# Protolink_Agro_LoRa_Schematic.net
KiCad netlist of a schematic drawn in Altium Designer
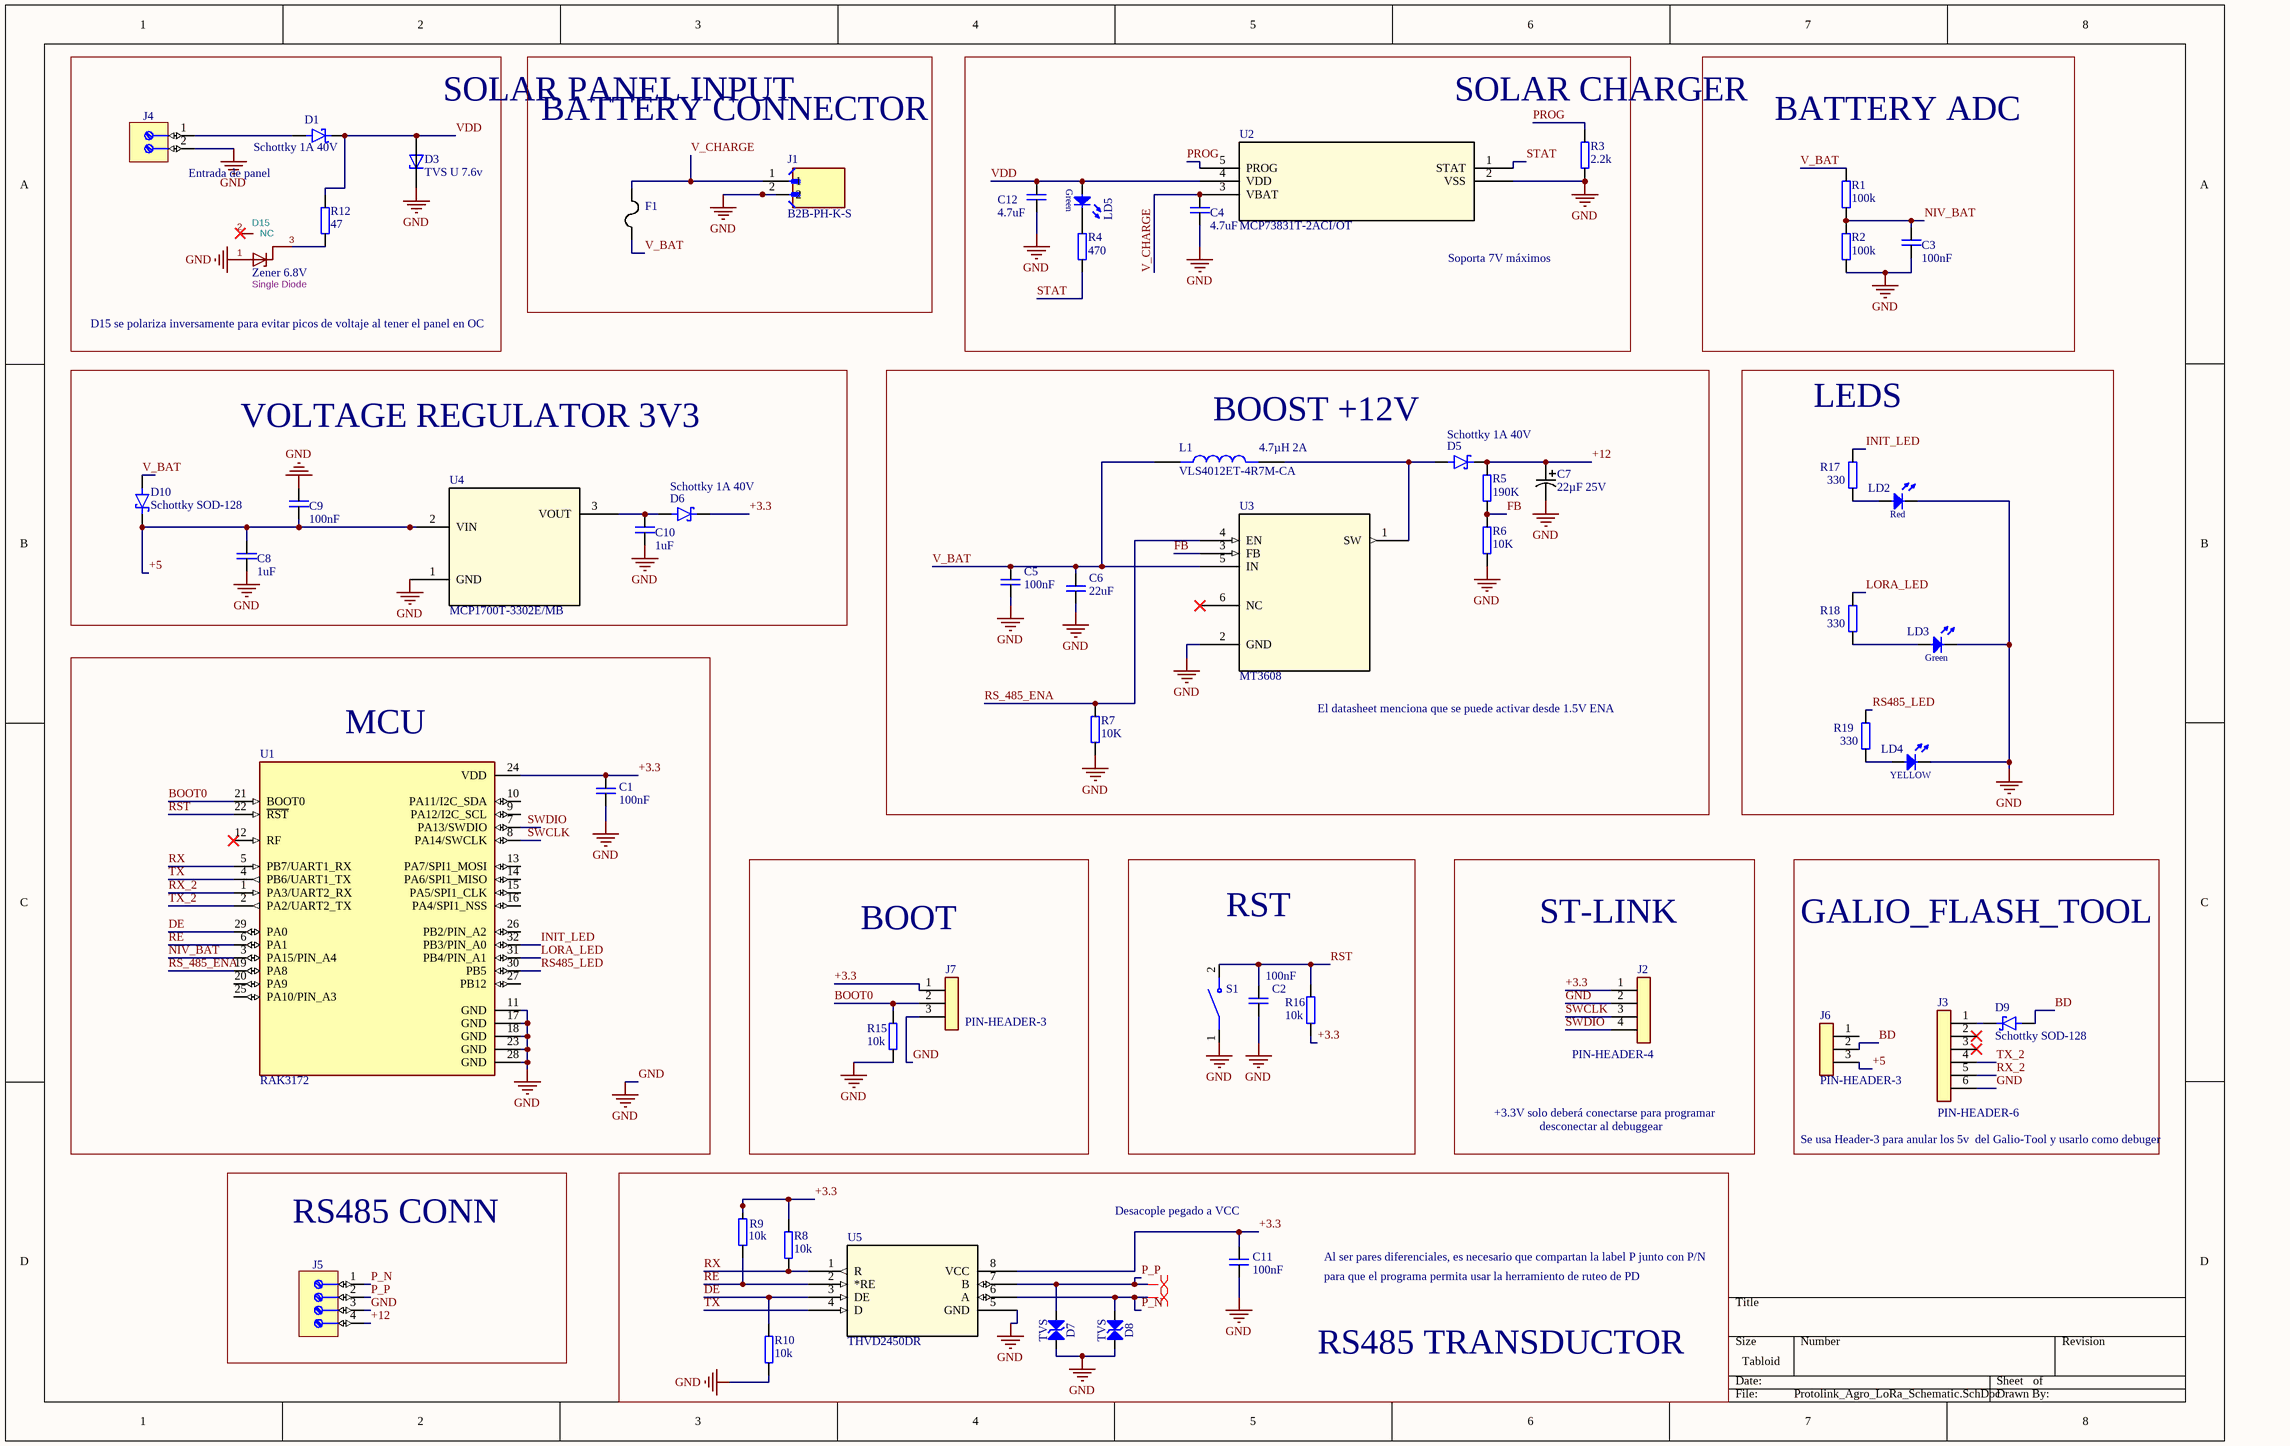
[diagram p0: Protolink_Agro_LoRa_Schematic.SchDoc]

(export (version "E")
  (design (tool "Eeschema 10.0.6"))
  (components
    (comp (ref "C1")
      (value "100nF")
      (footprint "CAPC2012X110N")
      (description "CAPACITOR, 0805")
      (fields (field (name "MF") "KEMET") (field (name "MP") "C0805C125K4RACTU"))
      (libsource (lib "") (part "C0805C125K4RACTU_1"))
    )
    (comp (ref "C2")
      (value "100nF")
      (footprint "CAPC2012X110N")
      (description "CAPACITOR, 0805")
      (fields (field (name "MF") "KEMET") (field (name "MP") "C0805C125K4RACTU"))
      (libsource (lib "") (part "C0805C125K4RACTU_1"))
    )
    (comp (ref "C3")
      (value "100nF")
      (footprint "CAPC2012X110N")
      (description "CAPACITOR, 0805")
      (fields (field (name "MF") "KEMET") (field (name "MP") "C0805C125K4RACTU"))
      (libsource (lib "") (part "C0805C125K4RACTU_1"))
    )
    (comp (ref "C4")
      (value "4.7uF")
      (footprint "CAPC2012X110N")
      (description "CAPACITOR, 0805")
      (fields (field (name "MF") "KEMET") (field (name "MP") "C0805C125K4RACTU"))
      (libsource (lib "Galio-complete") (part "C0805C125K4RACTU"))
    )
    (comp (ref "C5")
      (value "100nF")
      (footprint "CAPC2012X110N")
      (description "CAPACITOR, 0805")
      (fields (field (name "MF") "KEMET") (field (name "MP") "C0805C125K4RACTU"))
      (libsource (lib "") (part "C0805C125K4RACTU_1"))
    )
    (comp (ref "C6")
      (value "22uF")
      (footprint "CAPC2012X110N")
      (description "CAPACITOR, 0805")
      (fields (field (name "MF") "KEMET") (field (name "MP") "C0805C125K4RACTU"))
      (libsource (lib "") (part "C0805C125K4RACTU_1"))
    )
    (comp (ref "C7")
      (value "22µF 25V")
      (footprint "CAP_EEFK_C_PAN")
      (description "Capacitor electrolítico aluminio SMD")
      (fields
        (field (name "MANUFACTURER_PART_NUMBER") "EEE-FK1E220AR")
        (field (name "COPYRIGHT") "Copyright (C) 2026 Ultra Librarian. All rights reserved.")
      )
      (libsource (lib "Galio-complete") (part "EEE-FK1E220AR"))
    )
    (comp (ref "C8")
      (value "1uF")
      (footprint "CAPC2012X110N")
      (description "CAPACITOR, 0805")
      (fields (field (name "MF") "KEMET") (field (name "MP") "C0805C125K4RACTU"))
      (libsource (lib "") (part "C0805C125K4RACTU_1"))
    )
    (comp (ref "C9")
      (value "100nF")
      (footprint "CAPC2012X110N")
      (description "CAPACITOR, 0805")
      (fields (field (name "MF") "KEMET") (field (name "MP") "C0805C125K4RACTU"))
      (libsource (lib "") (part "C0805C125K4RACTU_1"))
    )
    (comp (ref "C10")
      (value "1uF")
      (footprint "CAPC2012X110N")
      (description "CAPACITOR, 0805")
      (fields (field (name "MF") "KEMET") (field (name "MP") "C0805C125K4RACTU"))
      (libsource (lib "") (part "C0805C125K4RACTU_1"))
    )
    (comp (ref "C11")
      (value "100nF")
      (footprint "CAPC2012X110N")
      (description "CAPACITOR, 0805")
      (fields (field (name "MF") "KEMET") (field (name "MP") "C0805C125K4RACTU"))
      (libsource (lib "") (part "C0805C125K4RACTU_1"))
    )
    (comp (ref "C12")
      (value "4.7uF")
      (footprint "CAPC2012X110N")
      (description "CAPACITOR, 0805")
      (fields (field (name "MF") "KEMET") (field (name "MP") "C0805C125K4RACTU"))
      (libsource (lib "Galio-complete") (part "C0805C125K4RACTU"))
    )
    (comp (ref "D1")
      (value "Schottky 1A 40V")
      (footprint "SODFL4725X110N")
      (description "Diode Schottky 40V 2A Surface Mount SOD-128/CFP5")
      (fields (field (name "MF") "Nexperia USA") (field (name "MP") "PMEG4020ETP,115"))
      (libsource (lib "Galio-complete") (part "PMEG4020ETP,115"))
    )
    (comp (ref "D3")
      (value "TVS U 7.6v")
      (footprint "DIOM4325X250N")
      (description "11 TVS Diode Surface Mount DO-214AC (SMA)")
      (fields (field (name "MF") "Bourns") (field (name "MP") "SMAJ11A"))
      (libsource (lib "Galio-complete") (part "SMAJ11A"))
    )
    (comp (ref "D5")
      (value "Schottky 1A 40V")
      (footprint "SODFL4725X110N")
      (description "Diode Schottky 40V 2A Surface Mount SOD-128/CFP5")
      (fields (field (name "MF") "Nexperia USA") (field (name "MP") "PMEG4020ETP,115"))
      (libsource (lib "Galio-complete") (part "PMEG4020ETP,115"))
    )
    (comp (ref "D6")
      (value "Schottky 1A 40V")
      (footprint "SODFL4725X110N")
      (description "Diode Schottky 40V 2A Surface Mount SOD-128/CFP5")
      (fields (field (name "MF") "Nexperia USA") (field (name "MP") "PMEG4020ETP,115"))
      (libsource (lib "Galio-complete") (part "PMEG4020ETP,115"))
    )
    (comp (ref "D7")
      (value "TVS")
      (footprint "DIOM5126X229N")
      (description "Transient Voltage Suppressor Diode (Bi-Directional)")
      (libsource (lib "Galio-complete") (part "Diode TVS Bi-Directional"))
    )
    (comp (ref "D8")
      (value "TVS")
      (footprint "DIOM5126X229N")
      (description "Transient Voltage Suppressor Diode (Bi-Directional)")
      (libsource (lib "Galio-complete") (part "Diode TVS Bi-Directional"))
    )
    (comp (ref "D9")
      (value "Schottky SOD-128")
      (footprint "SODFL4725X110N")
      (description "Diode Schottky 40V 2A Surface Mount SOD-128/CFP5")
      (fields (field (name "MF") "Nexperia USA") (field (name "MP") "PMEG4020ETP,115"))
      (libsource (lib "Galio-complete") (part "PMEG4020ETP,115"))
    )
    (comp (ref "D10")
      (value "Schottky SOD-128")
      (footprint "SODFL4725X110N")
      (description "Diode Schottky 40V 2A Surface Mount SOD-128/CFP5")
      (fields (field (name "MF") "Nexperia USA") (field (name "MP") "PMEG4020ETP,115"))
      (libsource (lib "Galio-complete") (part "PMEG4020ETP,115"))
    )
    (comp (ref "D15")
      (value "Zener 6.8V")
      (footprint "SOT-23")
      (fields (field (name "ALTIUM_VALUE") "Single Diode"))
      (libsource (lib "Galio-complete") (part "Zener-Diode_NC"))
    )
    (comp (ref "F1")
      (value "~")
      (footprint "FUSE_MF-MSMF07524-2_BRN")
      (description "Fuse")
      (fields
        (field (name "MANUFACTURER_PART_NUMBER") "MF-MSMF075/24-2")
        (field (name "COPYRIGHT") "Copyright (C) 2026 Ultra Librarian. All rights reserved.")
      )
      (libsource (lib "Galio-complete") (part "MF-MSMF07524-2"))
    )
    (comp (ref "J1")
      (value "B2B-PH-K-S")
      (footprint "JST_B2B-PH-K-S")
      (description "Connector Header Through Hole 2 position 0.079 (2.00mm)")
      (fields (field (name "MF") "JST Sales America Inc."))
      (libsource (lib "Galio-connectors") (part "B2B-PH-K-S"))
    )
    (comp (ref "J2")
      (value "PIN-HEADER-4")
      (footprint "PIN-HEADER-4-MALE")
      (fields (field (name "MP") "MTSW-104-06-T-S-100"))
      (libsource (lib "Galio-connectors") (part "PIN-HEADER-4"))
    )
    (comp (ref "J3")
      (value "PIN-HEADER-6")
      (footprint "PIN-HEADER-6-FEMALE")
      (fields (field (name "MP") "MTSW-106-06-T-S-100"))
      (libsource (lib "Galio-connectors") (part "PIN-HEADER-6"))
    )
    (comp (ref "J4")
      (value "TRT2")
      (footprint "TRT_2_KF301")
      (description "Terminal Block, 2 Positions, Screw Connection")
      (libsource (lib "Galio-connectors") (part "TRT_2"))
    )
    (comp (ref "J5")
      (value "TRT4")
      (footprint "TRT_4_ KF301")
      (description "TRT_4")
      (libsource (lib "Galio-connectors") (part "TRT_4"))
    )
    (comp (ref "J6")
      (value "PIN-HEADER-3")
      (footprint "PIN-HEADER-3-MALE")
      (fields (field (name "MP") "MTSW-103-06-T-S-190"))
      (libsource (lib "Galio-connectors") (part "PIN-HEADER-3"))
    )
    (comp (ref "J7")
      (value "PIN-HEADER-3")
      (footprint "PIN-HEADER-3-MALE")
      (fields (field (name "MP") "MTSW-103-06-T-S-190"))
      (libsource (lib "") (part "PIN-HEADER-3_1"))
    )
    (comp (ref "L1")
      (value "VLS4012ET-4R7M-CA")
      (footprint "IND_VLS4012ET-4R7M-CA")
      (description "4.7 µH Shielded Drum Core, Wirewound Inductor 1.9 A 118mOhm Max Nonstandard")
      (fields (field (name "MF") "TDK"))
      (libsource (lib "Galio-complete") (part "VLS4012ET-4R7M-CA"))
    )
    (comp (ref "LD2")
      (value "~")
      (footprint "LEDC2012X70N")
      (description "LED Red 0805")
      (libsource (lib "Galio-complete") (part "LED Red 0805"))
    )
    (comp (ref "LD3")
      (value "~")
      (footprint "LEDC2012X70N")
      (description "LED Green 0805")
      (libsource (lib "Galio-complete") (part "LED Green 0805"))
    )
    (comp (ref "LD4")
      (value "~")
      (footprint "LEDC2012X70N")
      (description "LED Yellow 0805")
      (libsource (lib "Galio-complete") (part "LED Yellow 0805"))
    )
    (comp (ref "LD5")
      (value "~")
      (footprint "LEDC2012X70N")
      (description "LED Green 0805")
      (libsource (lib "Galio-complete") (part "LED Green 0805"))
    )
    (comp (ref "R1")
      (value "100k")
      (footprint "RESC2013X84N")
      (libsource (lib "Galio-complete") (part "RES"))
    )
    (comp (ref "R2")
      (value "100k")
      (footprint "RESC2013X84N")
      (libsource (lib "Galio-complete") (part "RES"))
    )
    (comp (ref "R3")
      (value "2.2k")
      (footprint "RESC2013X84N")
      (libsource (lib "Galio-complete") (part "RES"))
    )
    (comp (ref "R4") (value "470") (footprint "RESC2013X84N") (libsource (lib "Galio-complete") (part "RES")))
    (comp (ref "R5")
      (value "190K")
      (footprint "RESC2013X84N")
      (libsource (lib "Galio-complete") (part "RES"))
    )
    (comp (ref "R6") (value "10K") (footprint "RESC2013X84N") (libsource (lib "Galio-complete") (part "RES")))
    (comp (ref "R7") (value "10K") (footprint "RESC2013X84N") (libsource (lib "Galio-complete") (part "RES")))
    (comp (ref "R8") (value "10k") (footprint "RESC2013X84N") (libsource (lib "Galio-complete") (part "RES")))
    (comp (ref "R9") (value "10k") (footprint "RESC2013X84N") (libsource (lib "Galio-complete") (part "RES")))
    (comp (ref "R10")
      (value "10k")
      (footprint "RESC2013X84N")
      (libsource (lib "Galio-complete") (part "RES"))
    )
    (comp (ref "R12") (value "47") (footprint "RESC2013X84N") (libsource (lib "Galio-complete") (part "RES")))
    (comp (ref "R15")
      (value "10k")
      (footprint "RESC2013X84N")
      (libsource (lib "Galio-complete") (part "RES"))
    )
    (comp (ref "R16")
      (value "10k")
      (footprint "RESC2013X84N")
      (libsource (lib "Galio-complete") (part "RES"))
    )
    (comp (ref "R17")
      (value "330")
      (footprint "RESC2013X84N")
      (libsource (lib "Galio-complete") (part "RES"))
    )
    (comp (ref "R18")
      (value "330")
      (footprint "RESC2013X84N")
      (libsource (lib "Galio-complete") (part "RES"))
    )
    (comp (ref "R19")
      (value "330")
      (footprint "RESC2013X84N")
      (libsource (lib "Galio-complete") (part "RES"))
    )
    (comp (ref "S1")
      (value "~")
      (footprint "SWITCH-SMD-4x3mm")
      (fields (field (name "MF") "Xunpu") (field (name "MP") "TS-1088-AR02016"))
      (libsource (lib "Galio-complete") (part "SWITCH-SMD-4x3mm"))
    )
    (comp (ref "U1")
      (value "RAK3172")
      (footprint "XCVR_RAK3172")
      (fields (field (name "MF") "Shenzhen RAKwireless Technology Co.,Ltd."))
      (libsource (lib "Galio-modules") (part "RAK3172"))
    )
    (comp (ref "U2")
      (value "MCP73831T-2ACI/OT")
      (footprint "SOT-23-5_MC_MCH-M")
      (description "Series Single-Cell Li-Ion/Li-Polymer Battery Charge Controller")
      (fields (field (name "COPYRIGHT") "Copyright (C) 2025 Ultra Librarian. All rights reserved."))
      (libsource (lib "Galio-complete") (part "MCP73831T-2ACIOT"))
    )
    (comp (ref "U3")
      (value "MT3608")
      (footprint "TSOT23-6SOT23-6_AER")
      (description "DC-DC step-up")
      (fields (field (name "COPYRIGHT") "Copyright (C) 2025 Ultra Librarian. All rights reserved."))
      (libsource (lib "Galio-complete") (part "MT3608"))
    )
    (comp (ref "U4")
      (value "MCP1700T-3302E/MB")
      (footprint "SOT-89_3MC_MCH")
      (description "Linear Voltage Regulators")
      (fields (field (name "COPYRIGHT") "Copyright (C) 2026 Ultra Librarian. All rights reserved."))
      (libsource (lib "Galio-complete") (part "MCP1700T-3302EMB"))
    )
    (comp (ref "U5")
      (value "THVD2450DR")
      (footprint "SOIC8-N_MC")
      (description "Transceiver Half RS422, RS485 SOIC-8")
      (fields (field (name "COPYRIGHT") "Copyright (C) 2025 Ultra Librarian. All rights reserved."))
      (libsource (lib "Galio-complete") (part "THVD2450DR"))
    )
  )
  (nets
    (net (code "1") (name "/+3.3") (class "Default")
      (node (ref "C1") (pin "2") (pinfunction "2_2") (pintype "passive"))
      (node (ref "C11") (pin "2") (pinfunction "2_2") (pintype "passive"))
      (node (ref "D6") (pin "1") (pinfunction "K_1") (pintype "passive"))
      (node (ref "J2") (pin "1") (pintype "passive"))
      (node (ref "J7") (pin "1") (pintype "passive"))
      (node (ref "R16") (pin "1") (pinfunction "1_1") (pintype "passive"))
      (node (ref "R8") (pin "2") (pinfunction "2_2") (pintype "passive"))
      (node (ref "R9") (pin "2") (pinfunction "2_2") (pintype "passive"))
      (node (ref "U1") (pin "24") (pinfunction "VDD_24") (pintype "power_in"))
      (node (ref "U5") (pin "8") (pinfunction "VCC_8") (pintype "power_in"))
    )
    (net (code "2") (name "/+5") (class "Default")
      (node (ref "C8") (pin "2") (pinfunction "2_2") (pintype "passive"))
      (node (ref "C9") (pin "1") (pinfunction "1_1") (pintype "passive"))
      (node (ref "D10") (pin "1") (pinfunction "K_1") (pintype "passive"))
      (node (ref "J6") (pin "3") (pintype "passive"))
      (node (ref "U4") (pin "2") (pinfunction "VIN_2") (pintype "passive"))
    )
    (net (code "3") (name "/+12") (class "Default")
      (node (ref "C7") (pin "1") (pinfunction "1_1") (pintype "passive"))
      (node (ref "D5") (pin "1") (pinfunction "K_1") (pintype "passive"))
      (node (ref "J5") (pin "4") (pinfunction "4_4") (pintype "bidirectional"))
      (node (ref "R5") (pin "2") (pinfunction "2_2") (pintype "passive"))
    )
    (net (code "4") (name "/BD") (class "Default")
      (node (ref "D9") (pin "2") (pinfunction "A_2") (pintype "passive"))
      (node (ref "J6") (pin "2") (pintype "passive"))
    )
    (net (code "5") (name "/BOOT0") (class "Default")
      (node (ref "J7") (pin "2") (pintype "passive"))
      (node (ref "R15") (pin "2") (pinfunction "2_2") (pintype "passive"))
      (node (ref "U1") (pin "21") (pinfunction "BOOT0_21") (pintype "input"))
    )
    (net (code "6") (name "/DE") (class "Default")
      (node (ref "R10") (pin "2") (pinfunction "2_2") (pintype "passive"))
      (node (ref "U1") (pin "29") (pinfunction "PA0_29") (pintype "bidirectional"))
      (node (ref "U5") (pin "3") (pinfunction "DE_3") (pintype "input"))
    )
    (net (code "7") (name "/FB") (class "Default")
      (node (ref "R5") (pin "1") (pinfunction "1_1") (pintype "passive"))
      (node (ref "R6") (pin "2") (pinfunction "2_2") (pintype "passive"))
      (node (ref "U3") (pin "3") (pinfunction "FB_3") (pintype "input"))
    )
    (net (code "8") (name "/INIT_LED") (class "Default")
      (node (ref "R17") (pin "2") (pinfunction "2_2") (pintype "passive"))
      (node (ref "U1") (pin "32") (pinfunction "PB3/PIN_A0_32") (pintype "bidirectional"))
    )
    (net (code "9") (name "/LORA_LED") (class "Default")
      (node (ref "R18") (pin "2") (pinfunction "2_2") (pintype "passive"))
      (node (ref "U1") (pin "31") (pinfunction "PB4/PIN_A1_31") (pintype "bidirectional"))
    )
    (net (code "10") (name "/NIV_BAT") (class "Default")
      (node (ref "C3") (pin "2") (pinfunction "2_2") (pintype "passive"))
      (node (ref "R1") (pin "1") (pinfunction "1_1") (pintype "passive"))
      (node (ref "R2") (pin "2") (pinfunction "2_2") (pintype "passive"))
      (node (ref "U1") (pin "3") (pinfunction "PA15/PIN_A4_3") (pintype "bidirectional"))
    )
    (net (code "11") (name "/PROG") (class "Default")
      (node (ref "R3") (pin "2") (pinfunction "2_2") (pintype "passive"))
      (node (ref "U2") (pin "5") (pinfunction "PROG_5") (pintype "passive"))
    )
    (net (code "12") (name "/P_N") (class "Default")
      (node (ref "D8") (pin "2") (pinfunction "A_2") (pintype "passive"))
      (node (ref "J5") (pin "1") (pinfunction "1_1") (pintype "bidirectional"))
      (node (ref "U5") (pin "6") (pinfunction "A_6") (pintype "bidirectional"))
    )
    (net (code "13") (name "/P_P") (class "Default")
      (node (ref "D7") (pin "2") (pinfunction "A_2") (pintype "passive"))
      (node (ref "J5") (pin "2") (pinfunction "2_2") (pintype "bidirectional"))
      (node (ref "U5") (pin "7") (pinfunction "B_7") (pintype "bidirectional"))
    )
    (net (code "14") (name "/RE") (class "Default")
      (node (ref "R9") (pin "1") (pinfunction "1_1") (pintype "passive"))
      (node (ref "U1") (pin "6") (pinfunction "PA1_6") (pintype "bidirectional"))
      (node (ref "U5") (pin "2") (pinfunction "*RE_2") (pintype "input"))
    )
    (net (code "15") (name "/RS485_LED") (class "Default")
      (node (ref "R19") (pin "2") (pinfunction "2_2") (pintype "passive"))
      (node (ref "U1") (pin "30") (pinfunction "PB5_30") (pintype "bidirectional"))
    )
    (net (code "16") (name "/RST") (class "Default")
      (node (ref "C2") (pin "2") (pinfunction "2_2") (pintype "passive"))
      (node (ref "R16") (pin "2") (pinfunction "2_2") (pintype "passive"))
      (node (ref "S1") (pin "2") (pinfunction "2_2") (pintype "passive"))
      (node (ref "U1") (pin "22") (pinfunction "~{RST}_22") (pintype "input"))
    )
    (net (code "17") (name "/RS_485_ENA") (class "Default")
      (node (ref "R7") (pin "2") (pinfunction "2_2") (pintype "passive"))
      (node (ref "U1") (pin "19") (pinfunction "PA8_19") (pintype "bidirectional"))
      (node (ref "U3") (pin "4") (pinfunction "EN_4") (pintype "input"))
    )
    (net (code "18") (name "/RX") (class "Default")
      (node (ref "R8") (pin "1") (pinfunction "1_1") (pintype "passive"))
      (node (ref "U1") (pin "5") (pinfunction "PB7/UART1_RX_5") (pintype "input"))
      (node (ref "U5") (pin "1") (pinfunction "R_1") (pintype "output"))
    )
    (net (code "19") (name "/RX_2") (class "Default")
      (node (ref "J3") (pin "5") (pintype "passive"))
      (node (ref "U1") (pin "1") (pinfunction "PA3/UART2_RX_1") (pintype "input"))
    )
    (net (code "20") (name "/STAT") (class "Default")
      (node (ref "R4") (pin "1") (pinfunction "1_1") (pintype "passive"))
      (node (ref "U2") (pin "1") (pinfunction "STAT_1") (pintype "passive"))
    )
    (net (code "21") (name "/SWCLK") (class "Default")
      (node (ref "J2") (pin "3") (pintype "passive"))
      (node (ref "U1") (pin "8") (pinfunction "PA14/SWCLK_8") (pintype "bidirectional"))
    )
    (net (code "22") (name "/SWDIO") (class "Default")
      (node (ref "J2") (pin "4") (pintype "passive"))
      (node (ref "U1") (pin "7") (pinfunction "PA13/SWDIO_7") (pintype "bidirectional"))
    )
    (net (code "23") (name "/TX") (class "Default")
      (node (ref "U1") (pin "4") (pinfunction "PB6/UART1_TX_4") (pintype "output"))
      (node (ref "U5") (pin "4") (pinfunction "D_4") (pintype "input"))
    )
    (net (code "24") (name "/TX_2") (class "Default")
      (node (ref "J3") (pin "4") (pintype "passive"))
      (node (ref "U1") (pin "2") (pinfunction "PA2/UART2_TX_2") (pintype "output"))
    )
    (net (code "25") (name "/VDD") (class "Default")
      (node (ref "C12") (pin "2") (pinfunction "2_2") (pintype "passive"))
      (node (ref "D1") (pin "1") (pinfunction "K_1") (pintype "passive"))
      (node (ref "D3") (pin "A") (pinfunction "A_A") (pintype "passive"))
      (node (ref "LD5") (pin "2") (pinfunction "A_2") (pintype "passive"))
      (node (ref "R12") (pin "2") (pinfunction "2_2") (pintype "passive"))
      (node (ref "U2") (pin "4") (pinfunction "VDD_4") (pintype "passive"))
    )
    (net (code "26") (name "/V_BAT") (class "Default")
      (node (ref "C5") (pin "2") (pinfunction "2_2") (pintype "passive"))
      (node (ref "C6") (pin "2") (pinfunction "2_2") (pintype "passive"))
      (node (ref "D10") (pin "2") (pinfunction "A_2") (pintype "passive"))
      (node (ref "F1") (pin "1") (pinfunction "1_1") (pintype "passive"))
      (node (ref "L1") (pin "1") (pinfunction "1_1") (pintype "passive"))
      (node (ref "R1") (pin "2") (pinfunction "2_2") (pintype "passive"))
      (node (ref "U3") (pin "5") (pinfunction "IN_5") (pintype "power_in"))
    )
    (net (code "27") (name "/V_CHARGE") (class "Default")
      (node (ref "C4") (pin "2") (pinfunction "2_2") (pintype "passive"))
      (node (ref "F1") (pin "2") (pinfunction "2_2") (pintype "passive"))
      (node (ref "J1") (pin "1") (pinfunction "1_1") (pintype "passive"))
      (node (ref "U2") (pin "3") (pinfunction "VBAT_3") (pintype "passive"))
    )
    (net (code "28") (name "GND") (class "Default")
      (node (ref "C1") (pin "1") (pinfunction "1_1") (pintype "passive"))
      (node (ref "C10") (pin "1") (pinfunction "1_1") (pintype "passive"))
      (node (ref "C11") (pin "1") (pinfunction "1_1") (pintype "passive"))
      (node (ref "C12") (pin "1") (pinfunction "1_1") (pintype "passive"))
      (node (ref "C2") (pin "1") (pinfunction "1_1") (pintype "passive"))
      (node (ref "C3") (pin "1") (pinfunction "1_1") (pintype "passive"))
      (node (ref "C4") (pin "1") (pinfunction "1_1") (pintype "passive"))
      (node (ref "C5") (pin "1") (pinfunction "1_1") (pintype "passive"))
      (node (ref "C6") (pin "1") (pinfunction "1_1") (pintype "passive"))
      (node (ref "C7") (pin "2") (pinfunction "2_2") (pintype "passive"))
      (node (ref "C8") (pin "1") (pinfunction "1_1") (pintype "passive"))
      (node (ref "C9") (pin "2") (pinfunction "2_2") (pintype "passive"))
      (node (ref "D15") (pin "1") (pinfunction "A_1") (pintype "passive"))
      (node (ref "D3") (pin "C") (pinfunction "C_C") (pintype "passive"))
      (node (ref "D7") (pin "1") (pinfunction "C_1") (pintype "passive"))
      (node (ref "D8") (pin "1") (pinfunction "C_1") (pintype "passive"))
      (node (ref "J1") (pin "2") (pinfunction "2_2") (pintype "passive"))
      (node (ref "J2") (pin "2") (pintype "passive"))
      (node (ref "J3") (pin "6") (pintype "passive"))
      (node (ref "J4") (pin "2") (pinfunction "2_2") (pintype "bidirectional"))
      (node (ref "J5") (pin "3") (pinfunction "3_3") (pintype "bidirectional"))
      (node (ref "J7") (pin "3") (pintype "passive"))
      (node (ref "LD2") (pin "1") (pinfunction "C_1") (pintype "passive"))
      (node (ref "LD3") (pin "1") (pinfunction "C_1") (pintype "passive"))
      (node (ref "LD4") (pin "1") (pinfunction "C_1") (pintype "passive"))
      (node (ref "R10") (pin "1") (pinfunction "1_1") (pintype "passive"))
      (node (ref "R15") (pin "1") (pinfunction "1_1") (pintype "passive"))
      (node (ref "R2") (pin "1") (pinfunction "1_1") (pintype "passive"))
      (node (ref "R3") (pin "1") (pinfunction "1_1") (pintype "passive"))
      (node (ref "R6") (pin "1") (pinfunction "1_1") (pintype "passive"))
      (node (ref "R7") (pin "1") (pinfunction "1_1") (pintype "passive"))
      (node (ref "S1") (pin "1") (pinfunction "1_1") (pintype "passive"))
      (node (ref "U1") (pin "11") (pinfunction "GND_11") (pintype "power_in"))
      (node (ref "U1") (pin "17") (pinfunction "GND_17") (pintype "power_in"))
      (node (ref "U1") (pin "18") (pinfunction "GND_18") (pintype "power_in"))
      (node (ref "U1") (pin "23") (pinfunction "GND_23") (pintype "power_in"))
      (node (ref "U1") (pin "28") (pinfunction "GND_28") (pintype "power_in"))
      (node (ref "U2") (pin "2") (pinfunction "VSS_2") (pintype "passive"))
      (node (ref "U3") (pin "2") (pinfunction "GND_2") (pintype "power_in"))
      (node (ref "U4") (pin "1") (pinfunction "GND_1") (pintype "passive"))
      (node (ref "U5") (pin "5") (pinfunction "GND_5") (pintype "power_in"))
    )
    (net (code "29") (name "Net-(D1-A)") (class "Default")
      (node (ref "D1") (pin "2") (pinfunction "A_2") (pintype "passive"))
      (node (ref "J4") (pin "1") (pinfunction "1_1") (pintype "bidirectional"))
    )
    (net (code "30") (name "Net-(D5-A)") (class "Default")
      (node (ref "D5") (pin "2") (pinfunction "A_2") (pintype "passive"))
      (node (ref "L1") (pin "2") (pinfunction "2_2") (pintype "passive"))
      (node (ref "U3") (pin "1") (pinfunction "SW_1") (pintype "output"))
    )
    (net (code "31") (name "Net-(D6-A)") (class "Default")
      (node (ref "C10") (pin "2") (pinfunction "2_2") (pintype "passive"))
      (node (ref "D6") (pin "2") (pinfunction "A_2") (pintype "passive"))
      (node (ref "U4") (pin "3") (pinfunction "VOUT_3") (pintype "passive"))
    )
    (net (code "32") (name "Net-(D9-K)") (class "Default")
      (node (ref "D9") (pin "1") (pinfunction "K_1") (pintype "passive"))
      (node (ref "J3") (pin "1") (pintype "passive"))
    )
    (net (code "33") (name "Net-(D15-C)") (class "Default")
      (node (ref "D15") (pin "3") (pinfunction "C_3") (pintype "passive"))
      (node (ref "R12") (pin "1") (pinfunction "1_1") (pintype "passive"))
    )
    (net (code "34") (name "Net-(LD2-A)") (class "Default")
      (node (ref "LD2") (pin "2") (pinfunction "A_2") (pintype "passive"))
      (node (ref "R17") (pin "1") (pinfunction "1_1") (pintype "passive"))
    )
    (net (code "35") (name "Net-(LD3-A)") (class "Default")
      (node (ref "LD3") (pin "2") (pinfunction "A_2") (pintype "passive"))
      (node (ref "R18") (pin "1") (pinfunction "1_1") (pintype "passive"))
    )
    (net (code "36") (name "Net-(LD4-A)") (class "Default")
      (node (ref "LD4") (pin "2") (pinfunction "A_2") (pintype "passive"))
      (node (ref "R19") (pin "1") (pinfunction "1_1") (pintype "passive"))
    )
    (net (code "37") (name "Net-(LD5-C)") (class "Default")
      (node (ref "LD5") (pin "1") (pinfunction "C_1") (pintype "passive"))
      (node (ref "R4") (pin "2") (pinfunction "2_2") (pintype "passive"))
    )
    (net (code "38") (name "unconnected-(D15-NC-Pad2)") (class "Default")
      (node (ref "D15") (pin "2") (pinfunction "NC_2") (pintype "passive+no_connect"))
    )
    (net (code "39") (name "unconnected-(J3-Pad2)") (class "Default")
      (node (ref "J3") (pin "2") (pintype "passive+no_connect"))
    )
    (net (code "40") (name "unconnected-(J3-Pad3)") (class "Default")
      (node (ref "J3") (pin "3") (pintype "passive+no_connect"))
    )
    (net (code "41") (name "unconnected-(J6-Pad1)") (class "Default")
      (node (ref "J6") (pin "1") (pintype "passive"))
    )
    (net (code "42") (name "unconnected-(U1-PA4{slash}SPI1_NSS-Pad16)") (class "Default")
      (node (ref "U1") (pin "16") (pinfunction "PA4/SPI1_NSS_16") (pintype "bidirectional"))
    )
    (net (code "43") (name "unconnected-(U1-PA5{slash}SPI1_CLK-Pad15)") (class "Default")
      (node (ref "U1") (pin "15") (pinfunction "PA5/SPI1_CLK_15") (pintype "bidirectional"))
    )
    (net (code "44") (name "unconnected-(U1-PA6{slash}SPI1_MISO-Pad14)") (class "Default")
      (node (ref "U1") (pin "14") (pinfunction "PA6/SPI1_MISO_14") (pintype "bidirectional"))
    )
    (net (code "45") (name "unconnected-(U1-PA7{slash}SPI1_MOSI-Pad13)") (class "Default")
      (node (ref "U1") (pin "13") (pinfunction "PA7/SPI1_MOSI_13") (pintype "bidirectional"))
    )
    (net (code "46") (name "unconnected-(U1-PA9-Pad20)") (class "Default")
      (node (ref "U1") (pin "20") (pinfunction "PA9_20") (pintype "bidirectional"))
    )
    (net (code "47") (name "unconnected-(U1-PA10{slash}PIN_A3-Pad25)") (class "Default")
      (node (ref "U1") (pin "25") (pinfunction "PA10/PIN_A3_25") (pintype "bidirectional"))
    )
    (net (code "48") (name "unconnected-(U1-PA11{slash}I2C_SDA-Pad10)") (class "Default")
      (node (ref "U1") (pin "10") (pinfunction "PA11/I2C_SDA_10") (pintype "bidirectional"))
    )
    (net (code "49") (name "unconnected-(U1-PA12{slash}I2C_SCL-Pad9)") (class "Default")
      (node (ref "U1") (pin "9") (pinfunction "PA12/I2C_SCL_9") (pintype "bidirectional"))
    )
    (net (code "50") (name "unconnected-(U1-PB2{slash}PIN_A2-Pad26)") (class "Default")
      (node (ref "U1") (pin "26") (pinfunction "PB2/PIN_A2_26") (pintype "bidirectional"))
    )
    (net (code "51") (name "unconnected-(U1-PB12-Pad27)") (class "Default")
      (node (ref "U1") (pin "27") (pinfunction "PB12_27") (pintype "bidirectional"))
    )
    (net (code "52") (name "unconnected-(U1-RF-Pad12)") (class "Default")
      (node (ref "U1") (pin "12") (pinfunction "RF_12") (pintype "input+no_connect"))
    )
    (net (code "53") (name "unconnected-(U3-NC-Pad6)") (class "Default")
      (node (ref "U3") (pin "6") (pinfunction "NC_6") (pintype "passive+no_connect"))
    )
  )
)
